# trezor_v1_1.net
KiCad netlist of a schematic drawn in EAGLE
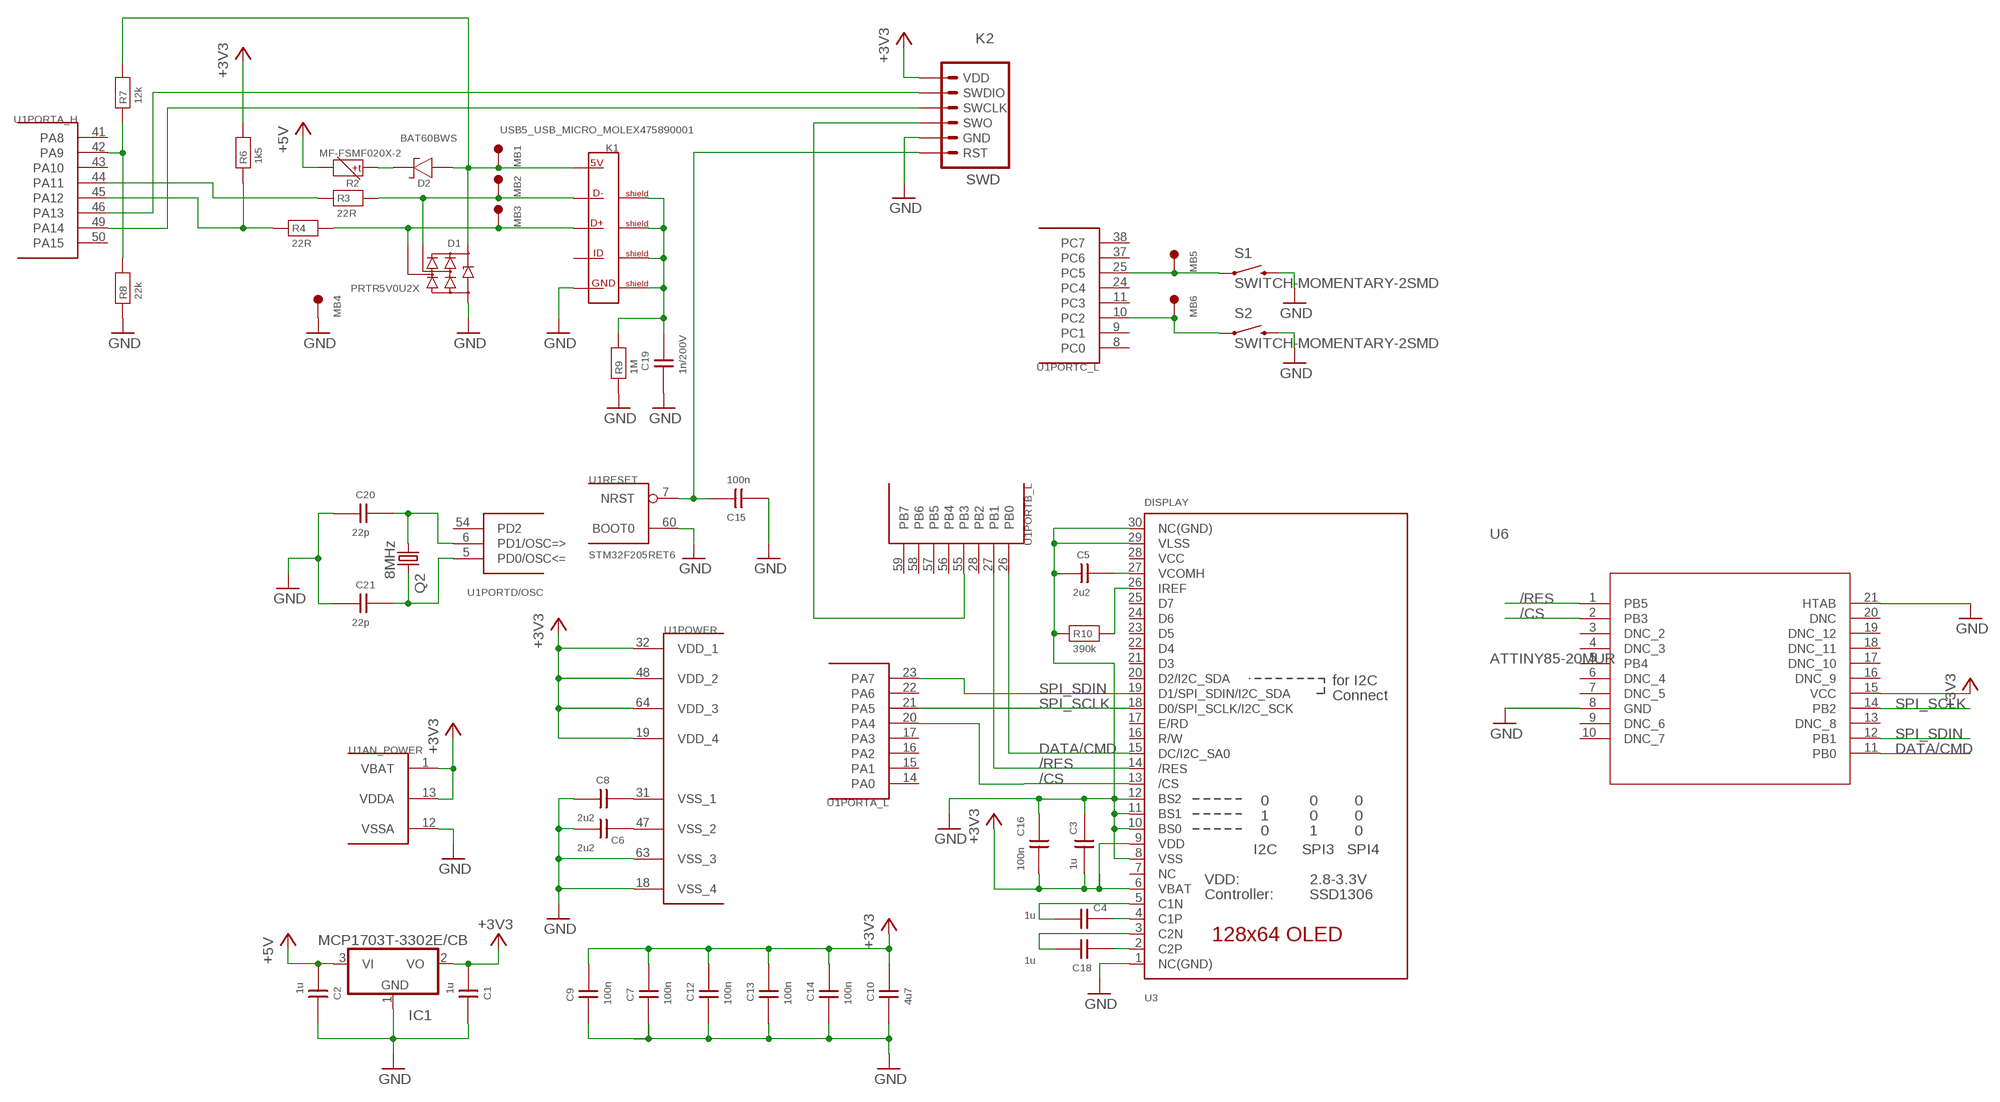
[diagram p0: schematic, sheet 1]

(export (version "E")
  (design (tool "Eeschema 10.0.6"))
  (components
    (comp (ref "C1")
      (value "1u")
      (footprint "eagle-import:0402")
      (libsource (lib "eagle-import") (part "C_0402"))
    )
    (comp (ref "C2")
      (value "1u")
      (footprint "eagle-import:0402")
      (libsource (lib "eagle-import") (part "C_0402"))
    )
    (comp (ref "C3")
      (value "1u")
      (footprint "eagle-import:0402")
      (libsource (lib "eagle-import") (part "C_0402"))
    )
    (comp (ref "C4")
      (value "1u")
      (footprint "eagle-import:0402")
      (libsource (lib "eagle-import") (part "C_0402"))
    )
    (comp (ref "C5")
      (value "2u2")
      (footprint "eagle-import:0603")
      (libsource (lib "eagle-import") (part "C_0603"))
    )
    (comp (ref "C6")
      (value "2u2")
      (footprint "eagle-import:0402")
      (libsource (lib "eagle-import") (part "C_0402"))
    )
    (comp (ref "C7")
      (value "100n")
      (footprint "eagle-import:0402")
      (libsource (lib "eagle-import") (part "C_0402"))
    )
    (comp (ref "C8")
      (value "2u2")
      (footprint "eagle-import:0402")
      (libsource (lib "eagle-import") (part "C_0402"))
    )
    (comp (ref "C9")
      (value "100n")
      (footprint "eagle-import:0402")
      (libsource (lib "eagle-import") (part "C_0402"))
    )
    (comp (ref "C10")
      (value "4u7")
      (footprint "eagle-import:0603")
      (libsource (lib "eagle-import") (part "C_0603"))
    )
    (comp (ref "C12")
      (value "100n")
      (footprint "eagle-import:0402")
      (libsource (lib "eagle-import") (part "C_0402"))
    )
    (comp (ref "C13")
      (value "100n")
      (footprint "eagle-import:0402")
      (libsource (lib "eagle-import") (part "C_0402"))
    )
    (comp (ref "C14")
      (value "100n")
      (footprint "eagle-import:0402")
      (libsource (lib "eagle-import") (part "C_0402"))
    )
    (comp (ref "C15")
      (value "100n")
      (footprint "eagle-import:0402")
      (libsource (lib "eagle-import") (part "C_0402"))
    )
    (comp (ref "C16")
      (value "100n")
      (footprint "eagle-import:0402")
      (libsource (lib "eagle-import") (part "C_0402"))
    )
    (comp (ref "C18")
      (value "1u")
      (footprint "eagle-import:0402")
      (libsource (lib "eagle-import") (part "C_0402"))
    )
    (comp (ref "C19")
      (value "1n/200V")
      (footprint "eagle-import:0603")
      (libsource (lib "eagle-import") (part "C_0603"))
    )
    (comp (ref "C20")
      (value "22p")
      (footprint "eagle-import:0402")
      (libsource (lib "eagle-import") (part "C_0402"))
    )
    (comp (ref "C21")
      (value "22p")
      (footprint "eagle-import:0402")
      (libsource (lib "eagle-import") (part "C_0402"))
    )
    (comp (ref "D1")
      (value "PRTR5V0U2X")
      (footprint "eagle-import:SOT143B")
      (libsource (lib "eagle-import") (part "PRTR5V0_SOT143B"))
    )
    (comp (ref "D2")
      (value "BAT60BWS")
      (footprint "eagle-import:SOD323")
      (libsource (lib "eagle-import") (part "DS_SOD323"))
    )
    (comp (ref "IC1")
      (value "MCP1703T-3302E/CB")
      (footprint "eagle-import:SOT23")
      (libsource (lib "eagle-import") (part "MCP1703CB"))
    )
    (comp (ref "K1")
      (value "USB5_USB_MICRO_MOLEX475890001")
      (footprint "eagle-import:USB_MICRO-MOLEX475890001")
      (libsource (lib "eagle-import") (part "USB5_USB_MICRO_MOLEX475890001"))
    )
    (comp (ref "K2")
      (value "SWD")
      (footprint "eagle-import:SWD")
      (libsource (lib "eagle-import") (part "SWD"))
    )
    (comp (ref "MB1")
      (value "MB_1.50")
      (footprint "eagle-import:MB1.5")
      (libsource (lib "eagle-import") (part "MB_1.50"))
    )
    (comp (ref "MB2")
      (value "MB_1.50")
      (footprint "eagle-import:MB1.5")
      (libsource (lib "eagle-import") (part "MB_1.50"))
    )
    (comp (ref "MB3")
      (value "MB_1.50")
      (footprint "eagle-import:MB1.5")
      (libsource (lib "eagle-import") (part "MB_1.50"))
    )
    (comp (ref "MB4")
      (value "MB_1.50")
      (footprint "eagle-import:MB1.5")
      (libsource (lib "eagle-import") (part "MB_1.50"))
    )
    (comp (ref "MB5")
      (value "MB_1.50")
      (footprint "eagle-import:MB1.5")
      (libsource (lib "eagle-import") (part "MB_1.50"))
    )
    (comp (ref "MB6")
      (value "MB_1.50")
      (footprint "eagle-import:MB1.5")
      (libsource (lib "eagle-import") (part "MB_1.50"))
    )
    (comp (ref "Q2")
      (value "8MHz")
      (footprint "eagle-import:CTS406")
      (libsource (lib "eagle-import") (part "CRYSTALCTS406"))
    )
    (comp (ref "R2")
      (value "MF-FSMF020X-2")
      (footprint "eagle-import:0603")
      (libsource (lib "eagle-import") (part "POLYSWITCH_0603"))
    )
    (comp (ref "R3")
      (value "22R")
      (footprint "eagle-import:0402")
      (libsource (lib "eagle-import") (part "R_0402"))
    )
    (comp (ref "R4")
      (value "22R")
      (footprint "eagle-import:0402")
      (libsource (lib "eagle-import") (part "R_0402"))
    )
    (comp (ref "R6")
      (value "1k5")
      (footprint "eagle-import:0402")
      (libsource (lib "eagle-import") (part "R_0402"))
    )
    (comp (ref "R7")
      (value "12k")
      (footprint "eagle-import:0402")
      (libsource (lib "eagle-import") (part "R_0402"))
    )
    (comp (ref "R8")
      (value "22k")
      (footprint "eagle-import:0402")
      (libsource (lib "eagle-import") (part "R_0402"))
    )
    (comp (ref "R9")
      (value "1M")
      (footprint "eagle-import:0603")
      (libsource (lib "eagle-import") (part "R_0603"))
    )
    (comp (ref "R10")
      (value "390k")
      (footprint "eagle-import:0402")
      (libsource (lib "eagle-import") (part "R_0402"))
    )
    (comp (ref "S1")
      (value "SWITCH-MOMENTARY-2SMD")
      (footprint "eagle-import:TACTILE_SWITCH_SMD")
      (libsource (lib "eagle-import") (part "SWITCH-MOMENTARY-2SMD"))
    )
    (comp (ref "S2")
      (value "SWITCH-MOMENTARY-2SMD")
      (footprint "eagle-import:TACTILE_SWITCH_SMD")
      (libsource (lib "eagle-import") (part "SWITCH-MOMENTARY-2SMD"))
    )
    (comp (ref "U1")
      (value "STM32F205RET6")
      (footprint "eagle-import:TQFP64")
      (libsource (lib "eagle-import") (part "STM32F10XRXT6"))
    )
    (comp (ref "U3")
      (value "DISPLAY")
      (footprint "eagle-import:UG-2864HSWEG01_0.96IN_WRAPAROUND")
      (libsource (lib "eagle-import") (part "DISP_OLED_UG-2864HSWEG010.96{dblquote}"))
    )
    (comp (ref "U6")
      (value "ATTINY85-20MUR")
      (footprint "eagle-import:20M1_ATM")
      (libsource (lib "eagle-import") (part "ATTINY85-20MUR"))
    )
  )
  (nets
    (net (code "1") (name "+3V3") (class "Default")
      (node (ref "C1") (pin "P$1") (pinfunction "1_P$1") (pintype "passive"))
      (node (ref "C10") (pin "2") (pinfunction "2_2") (pintype "passive"))
      (node (ref "C12") (pin "P$2") (pinfunction "2_P$2") (pintype "passive"))
      (node (ref "C13") (pin "P$2") (pinfunction "2_P$2") (pintype "passive"))
      (node (ref "C14") (pin "P$2") (pinfunction "2_P$2") (pintype "passive"))
      (node (ref "C16") (pin "P$1") (pinfunction "1_P$1") (pintype "passive"))
      (node (ref "C3") (pin "P$1") (pinfunction "1_P$1") (pintype "passive"))
      (node (ref "C7") (pin "P$2") (pinfunction "2_P$2") (pintype "passive"))
      (node (ref "C9") (pin "P$2") (pinfunction "2_P$2") (pintype "passive"))
      (node (ref "IC1") (pin "2") (pinfunction "VO_2") (pintype "passive"))
      (node (ref "K2") (pin "6") (pinfunction "VDD_6") (pintype "passive"))
      (node (ref "R6") (pin "P$2") (pinfunction "2_P$2") (pintype "passive"))
      (node (ref "U1") (pin "1") (pinfunction "VBAT_1") (pintype "power_in"))
      (node (ref "U1") (pin "13") (pinfunction "VDDA_13") (pintype "power_in"))
      (node (ref "U1") (pin "19") (pinfunction "VDD_4_19") (pintype "power_in"))
      (node (ref "U1") (pin "32") (pinfunction "VDD_1_32") (pintype "power_in"))
      (node (ref "U1") (pin "48") (pinfunction "VDD_2_48") (pintype "power_in"))
      (node (ref "U1") (pin "64") (pinfunction "VDD_3_64") (pintype "power_in"))
      (node (ref "U3") (pin "6") (pinfunction "VBAT_6") (pintype "input"))
      (node (ref "U3") (pin "9") (pinfunction "VDD_9") (pintype "power_in"))
      (node (ref "U6") (pin "15") (pinfunction "VCC_15") (pintype "passive"))
    )
    (net (code "2") (name "+5V") (class "Default")
      (node (ref "C2") (pin "P$1") (pinfunction "1_P$1") (pintype "passive"))
      (node (ref "IC1") (pin "3") (pinfunction "VI_3") (pintype "input"))
      (node (ref "R2") (pin "2") (pinfunction "2_2") (pintype "passive"))
    )
    (net (code "3") (name "/DATA{slash}CMD") (class "Default")
      (node (ref "U1") (pin "26") (pinfunction "PB0_26") (pintype "bidirectional"))
      (node (ref "U3") (pin "15") (pinfunction "DC/I2C_SA0_15") (pintype "input"))
      (node (ref "U6") (pin "11") (pinfunction "PB0_11") (pintype "passive"))
    )
    (net (code "4") (name "/SPI_SCLK") (class "Default")
      (node (ref "U1") (pin "21") (pinfunction "PA5_21") (pintype "bidirectional"))
      (node (ref "U3") (pin "18") (pinfunction "D0/SPI_SCLK/I2C_SCK_18") (pintype "bidirectional"))
      (node (ref "U6") (pin "14") (pinfunction "PB2_14") (pintype "passive"))
    )
    (net (code "5") (name "/SPI_SDIN") (class "Default")
      (node (ref "U1") (pin "23") (pinfunction "PA7_23") (pintype "bidirectional"))
      (node (ref "U3") (pin "19") (pinfunction "D1/SPI_SDIN/I2C_SDA_19") (pintype "bidirectional"))
      (node (ref "U6") (pin "12") (pinfunction "PB1_12") (pintype "passive"))
    )
    (net (code "6") (name "/VCC") (class "Default")
      (node (ref "U3") (pin "28") (pinfunction "VCC_28") (pintype "power_in"))
    )
    (net (code "7") (name "/{slash}CS") (class "Default")
      (node (ref "U1") (pin "20") (pinfunction "PA4_20") (pintype "bidirectional"))
      (node (ref "U3") (pin "13") (pinfunction "/CS_13") (pintype "input"))
      (node (ref "U6") (pin "2") (pinfunction "PB3_2") (pintype "passive"))
    )
    (net (code "8") (name "/{slash}RES") (class "Default")
      (node (ref "U1") (pin "27") (pinfunction "PB1_27") (pintype "bidirectional"))
      (node (ref "U3") (pin "14") (pinfunction "/RES_14") (pintype "input"))
      (node (ref "U6") (pin "1") (pinfunction "PB5_1") (pintype "passive"))
    )
    (net (code "9") (name "GND") (class "Default")
      (node (ref "C1") (pin "P$2") (pinfunction "2_P$2") (pintype "passive"))
      (node (ref "C10") (pin "1") (pinfunction "1_1") (pintype "passive"))
      (node (ref "C12") (pin "P$1") (pinfunction "1_P$1") (pintype "passive"))
      (node (ref "C13") (pin "P$1") (pinfunction "1_P$1") (pintype "passive"))
      (node (ref "C14") (pin "P$1") (pinfunction "1_P$1") (pintype "passive"))
      (node (ref "C15") (pin "P$1") (pinfunction "1_P$1") (pintype "passive"))
      (node (ref "C16") (pin "P$2") (pinfunction "2_P$2") (pintype "passive"))
      (node (ref "C19") (pin "1") (pinfunction "1_1") (pintype "passive"))
      (node (ref "C2") (pin "P$2") (pinfunction "2_P$2") (pintype "passive"))
      (node (ref "C20") (pin "P$1") (pinfunction "1_P$1") (pintype "passive"))
      (node (ref "C21") (pin "P$1") (pinfunction "1_P$1") (pintype "passive"))
      (node (ref "C3") (pin "P$2") (pinfunction "2_P$2") (pintype "passive"))
      (node (ref "C5") (pin "1") (pinfunction "1_1") (pintype "passive"))
      (node (ref "C6") (pin "P$1") (pinfunction "1_P$1") (pintype "passive"))
      (node (ref "C7") (pin "P$1") (pinfunction "1_P$1") (pintype "passive"))
      (node (ref "C8") (pin "P$1") (pinfunction "1_P$1") (pintype "passive"))
      (node (ref "C9") (pin "P$1") (pinfunction "1_P$1") (pintype "passive"))
      (node (ref "D1") (pin "1") (pinfunction "GND_1") (pintype "passive"))
      (node (ref "IC1") (pin "1") (pinfunction "GND_1") (pintype "passive"))
      (node (ref "K1") (pin "5") (pinfunction "5_GND_5") (pintype "bidirectional"))
      (node (ref "K2") (pin "2") (pinfunction "GND_2") (pintype "passive"))
      (node (ref "MB4") (pin "1") (pinfunction "1_1") (pintype "passive"))
      (node (ref "R10") (pin "P$1") (pinfunction "1_P$1") (pintype "passive"))
      (node (ref "R8") (pin "P$1") (pinfunction "1_P$1") (pintype "passive"))
      (node (ref "R9") (pin "1") (pinfunction "1_1") (pintype "passive"))
      (node (ref "S1") (pin "3") (pinfunction "2_3") (pintype "passive"))
      (node (ref "S1") (pin "4") (pinfunction "2_4") (pintype "passive"))
      (node (ref "S2") (pin "3") (pinfunction "2_3") (pintype "passive"))
      (node (ref "S2") (pin "4") (pinfunction "2_4") (pintype "passive"))
      (node (ref "U1") (pin "12") (pinfunction "VSSA_12") (pintype "power_in"))
      (node (ref "U1") (pin "18") (pinfunction "VSS_4_18") (pintype "power_in"))
      (node (ref "U1") (pin "60") (pinfunction "BOOT0_60") (pintype "input"))
      (node (ref "U1") (pin "63") (pinfunction "VSS_3_63") (pintype "power_in"))
      (node (ref "U3") (pin "1") (pinfunction "NC(GND)_1") (pintype "input"))
      (node (ref "U3") (pin "10") (pinfunction "BS0_10") (pintype "input"))
      (node (ref "U3") (pin "11") (pinfunction "BS1_11") (pintype "input"))
      (node (ref "U3") (pin "12") (pinfunction "BS2_12") (pintype "input"))
      (node (ref "U3") (pin "29") (pinfunction "VLSS_29") (pintype "power_in"))
      (node (ref "U3") (pin "30") (pinfunction "NC(GND)_30") (pintype "input"))
      (node (ref "U3") (pin "8") (pinfunction "VSS_8") (pintype "power_in"))
      (node (ref "U6") (pin "21") (pinfunction "HTAB_21") (pintype "passive"))
      (node (ref "U6") (pin "8") (pinfunction "GND_8") (pintype "passive"))
    )
    (net (code "10") (name "Net-(C4-1)") (class "Default")
      (node (ref "C4") (pin "P$1") (pinfunction "1_P$1") (pintype "passive"))
      (node (ref "U3") (pin "4") (pinfunction "C1P_4") (pintype "input"))
    )
    (net (code "11") (name "Net-(C4-2)") (class "Default")
      (node (ref "C4") (pin "P$2") (pinfunction "2_P$2") (pintype "passive"))
      (node (ref "U3") (pin "5") (pinfunction "C1N_5") (pintype "input"))
    )
    (net (code "12") (name "Net-(C6-2)") (class "Default")
      (node (ref "C6") (pin "P$2") (pinfunction "2_P$2") (pintype "passive"))
      (node (ref "U1") (pin "47") (pinfunction "VSS_2_47") (pintype "power_in"))
    )
    (net (code "13") (name "Net-(C8-2)") (class "Default")
      (node (ref "C8") (pin "P$2") (pinfunction "2_P$2") (pintype "passive"))
      (node (ref "U1") (pin "31") (pinfunction "VSS_1_31") (pintype "power_in"))
    )
    (net (code "14") (name "Net-(C15-2)") (class "Default")
      (node (ref "C15") (pin "P$2") (pinfunction "2_P$2") (pintype "passive"))
      (node (ref "K2") (pin "1") (pinfunction "RST_1") (pintype "passive"))
      (node (ref "U1") (pin "7") (pinfunction "NRST_7") (pintype "input"))
    )
    (net (code "15") (name "Net-(C18-1)") (class "Default")
      (node (ref "C18") (pin "P$1") (pinfunction "1_P$1") (pintype "passive"))
      (node (ref "U3") (pin "2") (pinfunction "C2P_2") (pintype "input"))
    )
    (net (code "16") (name "Net-(C18-2)") (class "Default")
      (node (ref "C18") (pin "P$2") (pinfunction "2_P$2") (pintype "passive"))
      (node (ref "U3") (pin "3") (pinfunction "C2N_3") (pintype "input"))
    )
    (net (code "17") (name "Net-(C19-Pad2)") (class "Default")
      (node (ref "C19") (pin "2") (pinfunction "2_2") (pintype "passive"))
      (node (ref "K1") (pin "S1_BOT") (pinfunction "SHIELD_1_S1_BOT") (pintype "passive"))
      (node (ref "K1") (pin "S1_TOP") (pinfunction "SHIELD_1_S1_TOP") (pintype "passive"))
      (node (ref "K1") (pin "S2_BOT") (pinfunction "SHIELD_2_S2_BOT") (pintype "passive"))
      (node (ref "K1") (pin "S2_TOP") (pinfunction "SHIELD_2_S2_TOP") (pintype "passive"))
      (node (ref "K1") (pin "S3_BOT") (pinfunction "SHIELD_3_S3_BOT") (pintype "passive"))
      (node (ref "K1") (pin "S3_TOP") (pinfunction "SHIELD_3_S3_TOP") (pintype "passive"))
      (node (ref "K1") (pin "S4_BOT") (pinfunction "SHIELD_4_S4_BOT") (pintype "passive"))
      (node (ref "K1") (pin "S4_TOP") (pinfunction "SHIELD_4_S4_TOP") (pintype "passive"))
      (node (ref "K1") (pin "SA") (pinfunction "SHIELD_1_SA") (pintype "passive"))
      (node (ref "K1") (pin "SB") (pinfunction "SHIELD_2_SB") (pintype "passive"))
      (node (ref "R9") (pin "2") (pinfunction "2_2") (pintype "passive"))
    )
    (net (code "18") (name "Net-(C20-2)") (class "Default")
      (node (ref "C20") (pin "P$2") (pinfunction "2_P$2") (pintype "passive"))
      (node (ref "Q2") (pin "1") (pinfunction "1_1") (pintype "passive"))
      (node (ref "U1") (pin "6") (pinfunction "PD1/OSC=>_6") (pintype "bidirectional"))
    )
    (net (code "19") (name "Net-(C21-2)") (class "Default")
      (node (ref "C21") (pin "P$2") (pinfunction "2_P$2") (pintype "passive"))
      (node (ref "Q2") (pin "3") (pinfunction "2_3") (pintype "passive"))
      (node (ref "U1") (pin "5") (pinfunction "PD0/OSC<=_5") (pintype "bidirectional"))
    )
    (net (code "20") (name "Net-(D1-I{slash}O1)") (class "Default")
      (node (ref "D1") (pin "2") (pinfunction "I/O1_2") (pintype "passive"))
      (node (ref "K1") (pin "2") (pinfunction "2_D-_2") (pintype "bidirectional"))
      (node (ref "MB2") (pin "1") (pinfunction "1_1") (pintype "passive"))
      (node (ref "R3") (pin "P$2") (pinfunction "2_P$2") (pintype "passive"))
    )
    (net (code "21") (name "Net-(D1-I{slash}O2)") (class "Default")
      (node (ref "D1") (pin "3") (pinfunction "I/O2_3") (pintype "passive"))
      (node (ref "K1") (pin "3") (pinfunction "3_D+_3") (pintype "bidirectional"))
      (node (ref "MB3") (pin "1") (pinfunction "1_1") (pintype "passive"))
      (node (ref "R4") (pin "P$2") (pinfunction "2_P$2") (pintype "passive"))
    )
    (net (code "22") (name "Net-(D1-VCC)") (class "Default")
      (node (ref "D1") (pin "4") (pinfunction "VCC_4") (pintype "passive"))
      (node (ref "D2") (pin "A") (pinfunction "1_A") (pintype "passive"))
      (node (ref "K1") (pin "1") (pinfunction "1_5V_1") (pintype "bidirectional"))
      (node (ref "MB1") (pin "1") (pinfunction "1_1") (pintype "passive"))
      (node (ref "R7") (pin "P$2") (pinfunction "2_P$2") (pintype "passive"))
    )
    (net (code "23") (name "Net-(D2-2)") (class "Default")
      (node (ref "D2") (pin "K") (pinfunction "2_K") (pintype "passive"))
      (node (ref "R2") (pin "1") (pinfunction "1_1") (pintype "passive"))
    )
    (net (code "24") (name "Net-(K2-SWCLK)") (class "Default")
      (node (ref "K2") (pin "4") (pinfunction "SWCLK_4") (pintype "passive"))
      (node (ref "U1") (pin "49") (pinfunction "PA14_49") (pintype "bidirectional"))
    )
    (net (code "25") (name "Net-(K2-SWDIO)") (class "Default")
      (node (ref "K2") (pin "5") (pinfunction "SWDIO_5") (pintype "passive"))
      (node (ref "U1") (pin "46") (pinfunction "PA13_46") (pintype "bidirectional"))
    )
    (net (code "26") (name "Net-(K2-SWO)") (class "Default")
      (node (ref "K2") (pin "3") (pinfunction "SWO_3") (pintype "passive"))
      (node (ref "U1") (pin "55") (pinfunction "PB3_55") (pintype "bidirectional"))
    )
    (net (code "27") (name "Net-(R3-1)") (class "Default")
      (node (ref "R3") (pin "P$1") (pinfunction "1_P$1") (pintype "passive"))
      (node (ref "U1") (pin "44") (pinfunction "PA11_44") (pintype "bidirectional"))
    )
    (net (code "28") (name "Net-(R4-1)") (class "Default")
      (node (ref "R4") (pin "P$1") (pinfunction "1_P$1") (pintype "passive"))
      (node (ref "R6") (pin "P$1") (pinfunction "1_P$1") (pintype "passive"))
      (node (ref "U1") (pin "45") (pinfunction "PA12_45") (pintype "bidirectional"))
    )
    (net (code "29") (name "Net-(R7-1)") (class "Default")
      (node (ref "R7") (pin "P$1") (pinfunction "1_P$1") (pintype "passive"))
      (node (ref "R8") (pin "P$2") (pinfunction "2_P$2") (pintype "passive"))
      (node (ref "U1") (pin "42") (pinfunction "PA9_42") (pintype "bidirectional"))
    )
    (net (code "30") (name "Net-(R10-2)") (class "Default")
      (node (ref "R10") (pin "P$2") (pinfunction "2_P$2") (pintype "passive"))
      (node (ref "U3") (pin "26") (pinfunction "IREF_26") (pintype "input"))
    )
    (net (code "31") (name "Net-(U1G-PC2)") (class "Default")
      (node (ref "MB6") (pin "1") (pinfunction "1_1") (pintype "passive"))
      (node (ref "S2") (pin "1") (pinfunction "1_1") (pintype "passive"))
      (node (ref "S2") (pin "2") (pinfunction "1_2") (pintype "passive"))
      (node (ref "U1") (pin "10") (pinfunction "PC2_10") (pintype "bidirectional"))
    )
    (net (code "32") (name "Net-(U1G-PC5)") (class "Default")
      (node (ref "MB5") (pin "1") (pinfunction "1_1") (pintype "passive"))
      (node (ref "S1") (pin "1") (pinfunction "1_1") (pintype "passive"))
      (node (ref "S1") (pin "2") (pinfunction "1_2") (pintype "passive"))
      (node (ref "U1") (pin "25") (pinfunction "PC5_25") (pintype "bidirectional"))
    )
    (net (code "33") (name "Net-(U3-VCOMH)") (class "Default")
      (node (ref "C5") (pin "2") (pinfunction "2_2") (pintype "passive"))
      (node (ref "U3") (pin "27") (pinfunction "VCOMH_27") (pintype "output"))
    )
    (net (code "34") (name "unconnected-(K1-4_ID-Pad4)") (class "Default")
      (node (ref "K1") (pin "4") (pinfunction "4_ID_4") (pintype "bidirectional"))
    )
    (net (code "35") (name "unconnected-(U1B-PA8-Pad41)") (class "Default")
      (node (ref "U1") (pin "41") (pinfunction "PA8_41") (pintype "bidirectional"))
    )
    (net (code "36") (name "unconnected-(U1B-PA10-Pad43)") (class "Default")
      (node (ref "U1") (pin "43") (pinfunction "PA10_43") (pintype "bidirectional"))
    )
    (net (code "37") (name "unconnected-(U1B-PA15-Pad50)") (class "Default")
      (node (ref "U1") (pin "50") (pinfunction "PA15_50") (pintype "bidirectional"))
    )
    (net (code "38") (name "unconnected-(U1C-PA0-Pad14)") (class "Default")
      (node (ref "U1") (pin "14") (pinfunction "PA0_14") (pintype "bidirectional"))
    )
    (net (code "39") (name "unconnected-(U1C-PA1-Pad15)") (class "Default")
      (node (ref "U1") (pin "15") (pinfunction "PA1_15") (pintype "bidirectional"))
    )
    (net (code "40") (name "unconnected-(U1C-PA2-Pad16)") (class "Default")
      (node (ref "U1") (pin "16") (pinfunction "PA2_16") (pintype "bidirectional"))
    )
    (net (code "41") (name "unconnected-(U1C-PA3-Pad17)") (class "Default")
      (node (ref "U1") (pin "17") (pinfunction "PA3_17") (pintype "bidirectional"))
    )
    (net (code "42") (name "unconnected-(U1C-PA6-Pad22)") (class "Default")
      (node (ref "U1") (pin "22") (pinfunction "PA6_22") (pintype "bidirectional"))
    )
    (net (code "43") (name "unconnected-(U1E-PB2-Pad28)") (class "Default")
      (node (ref "U1") (pin "28") (pinfunction "PB2_28") (pintype "bidirectional"))
    )
    (net (code "44") (name "unconnected-(U1E-PB4-Pad56)") (class "Default")
      (node (ref "U1") (pin "56") (pinfunction "PB4_56") (pintype "bidirectional"))
    )
    (net (code "45") (name "unconnected-(U1E-PB5-Pad57)") (class "Default")
      (node (ref "U1") (pin "57") (pinfunction "PB5_57") (pintype "bidirectional"))
    )
    (net (code "46") (name "unconnected-(U1E-PB6-Pad58)") (class "Default")
      (node (ref "U1") (pin "58") (pinfunction "PB6_58") (pintype "bidirectional"))
    )
    (net (code "47") (name "unconnected-(U1E-PB7-Pad59)") (class "Default")
      (node (ref "U1") (pin "59") (pinfunction "PB7_59") (pintype "bidirectional"))
    )
    (net (code "48") (name "unconnected-(U1G-PC0-Pad8)") (class "Default")
      (node (ref "U1") (pin "8") (pinfunction "PC0_8") (pintype "bidirectional"))
    )
    (net (code "49") (name "unconnected-(U1G-PC1-Pad9)") (class "Default")
      (node (ref "U1") (pin "9") (pinfunction "PC1_9") (pintype "bidirectional"))
    )
    (net (code "50") (name "unconnected-(U1G-PC3-Pad11)") (class "Default")
      (node (ref "U1") (pin "11") (pinfunction "PC3_11") (pintype "bidirectional"))
    )
    (net (code "51") (name "unconnected-(U1G-PC4-Pad24)") (class "Default")
      (node (ref "U1") (pin "24") (pinfunction "PC4_24") (pintype "bidirectional"))
    )
    (net (code "52") (name "unconnected-(U1G-PC6-Pad37)") (class "Default")
      (node (ref "U1") (pin "37") (pinfunction "PC6_37") (pintype "bidirectional"))
    )
    (net (code "53") (name "unconnected-(U1G-PC7-Pad38)") (class "Default")
      (node (ref "U1") (pin "38") (pinfunction "PC7_38") (pintype "bidirectional"))
    )
    (net (code "54") (name "unconnected-(U1H-PD2-Pad54)") (class "Default")
      (node (ref "U1") (pin "54") (pinfunction "PD2_54") (pintype "bidirectional"))
    )
    (net (code "55") (name "unconnected-(U3-D2{slash}I2C_SDA-Pad20)") (class "Default")
      (node (ref "U3") (pin "20") (pinfunction "D2/I2C_SDA_20") (pintype "bidirectional"))
    )
    (net (code "56") (name "unconnected-(U3-D3-Pad21)") (class "Default")
      (node (ref "U3") (pin "21") (pinfunction "D3_21") (pintype "bidirectional"))
    )
    (net (code "57") (name "unconnected-(U3-D4-Pad22)") (class "Default")
      (node (ref "U3") (pin "22") (pinfunction "D4_22") (pintype "bidirectional"))
    )
    (net (code "58") (name "unconnected-(U3-D5-Pad23)") (class "Default")
      (node (ref "U3") (pin "23") (pinfunction "D5_23") (pintype "bidirectional"))
    )
    (net (code "59") (name "unconnected-(U3-D6-Pad24)") (class "Default")
      (node (ref "U3") (pin "24") (pinfunction "D6_24") (pintype "bidirectional"))
    )
    (net (code "60") (name "unconnected-(U3-D7-Pad25)") (class "Default")
      (node (ref "U3") (pin "25") (pinfunction "D7_25") (pintype "bidirectional"))
    )
    (net (code "61") (name "unconnected-(U3-E{slash}RD-Pad17)") (class "Default")
      (node (ref "U3") (pin "17") (pinfunction "E/RD_17") (pintype "input"))
    )
    (net (code "62") (name "unconnected-(U3-NC-Pad7)") (class "Default")
      (node (ref "U3") (pin "7") (pinfunction "NC_7") (pintype "no_connect"))
    )
    (net (code "63") (name "unconnected-(U3-R{slash}W-Pad16)") (class "Default")
      (node (ref "U3") (pin "16") (pinfunction "R/W_16") (pintype "input"))
    )
    (net (code "64") (name "unconnected-(U6-DNC-Pad20)") (class "Default")
      (node (ref "U6") (pin "20") (pinfunction "DNC_20") (pintype "passive"))
    )
    (net (code "65") (name "unconnected-(U6-DNC_2-Pad3)") (class "Default")
      (node (ref "U6") (pin "3") (pinfunction "DNC_2_3") (pintype "passive"))
    )
    (net (code "66") (name "unconnected-(U6-DNC_3-Pad4)") (class "Default")
      (node (ref "U6") (pin "4") (pinfunction "DNC_3_4") (pintype "passive"))
    )
    (net (code "67") (name "unconnected-(U6-DNC_4-Pad6)") (class "Default")
      (node (ref "U6") (pin "6") (pinfunction "DNC_4_6") (pintype "passive"))
    )
    (net (code "68") (name "unconnected-(U6-DNC_5-Pad7)") (class "Default")
      (node (ref "U6") (pin "7") (pinfunction "DNC_5_7") (pintype "passive"))
    )
    (net (code "69") (name "unconnected-(U6-DNC_6-Pad9)") (class "Default")
      (node (ref "U6") (pin "9") (pinfunction "DNC_6_9") (pintype "passive"))
    )
    (net (code "70") (name "unconnected-(U6-DNC_7-Pad10)") (class "Default")
      (node (ref "U6") (pin "10") (pinfunction "DNC_7_10") (pintype "passive"))
    )
    (net (code "71") (name "unconnected-(U6-DNC_8-Pad13)") (class "Default")
      (node (ref "U6") (pin "13") (pinfunction "DNC_8_13") (pintype "passive"))
    )
    (net (code "72") (name "unconnected-(U6-DNC_9-Pad16)") (class "Default")
      (node (ref "U6") (pin "16") (pinfunction "DNC_9_16") (pintype "passive"))
    )
    (net (code "73") (name "unconnected-(U6-DNC_10-Pad17)") (class "Default")
      (node (ref "U6") (pin "17") (pinfunction "DNC_10_17") (pintype "passive"))
    )
    (net (code "74") (name "unconnected-(U6-DNC_11-Pad18)") (class "Default")
      (node (ref "U6") (pin "18") (pinfunction "DNC_11_18") (pintype "passive"))
    )
    (net (code "75") (name "unconnected-(U6-DNC_12-Pad19)") (class "Default")
      (node (ref "U6") (pin "19") (pinfunction "DNC_12_19") (pintype "passive"))
    )
    (net (code "76") (name "unconnected-(U6-PB4-Pad5)") (class "Default")
      (node (ref "U6") (pin "5") (pinfunction "PB4_5") (pintype "passive"))
    )
  )
)
